# PaxInstrument-T400.net
KiCad netlist of a schematic drawn in EAGLE
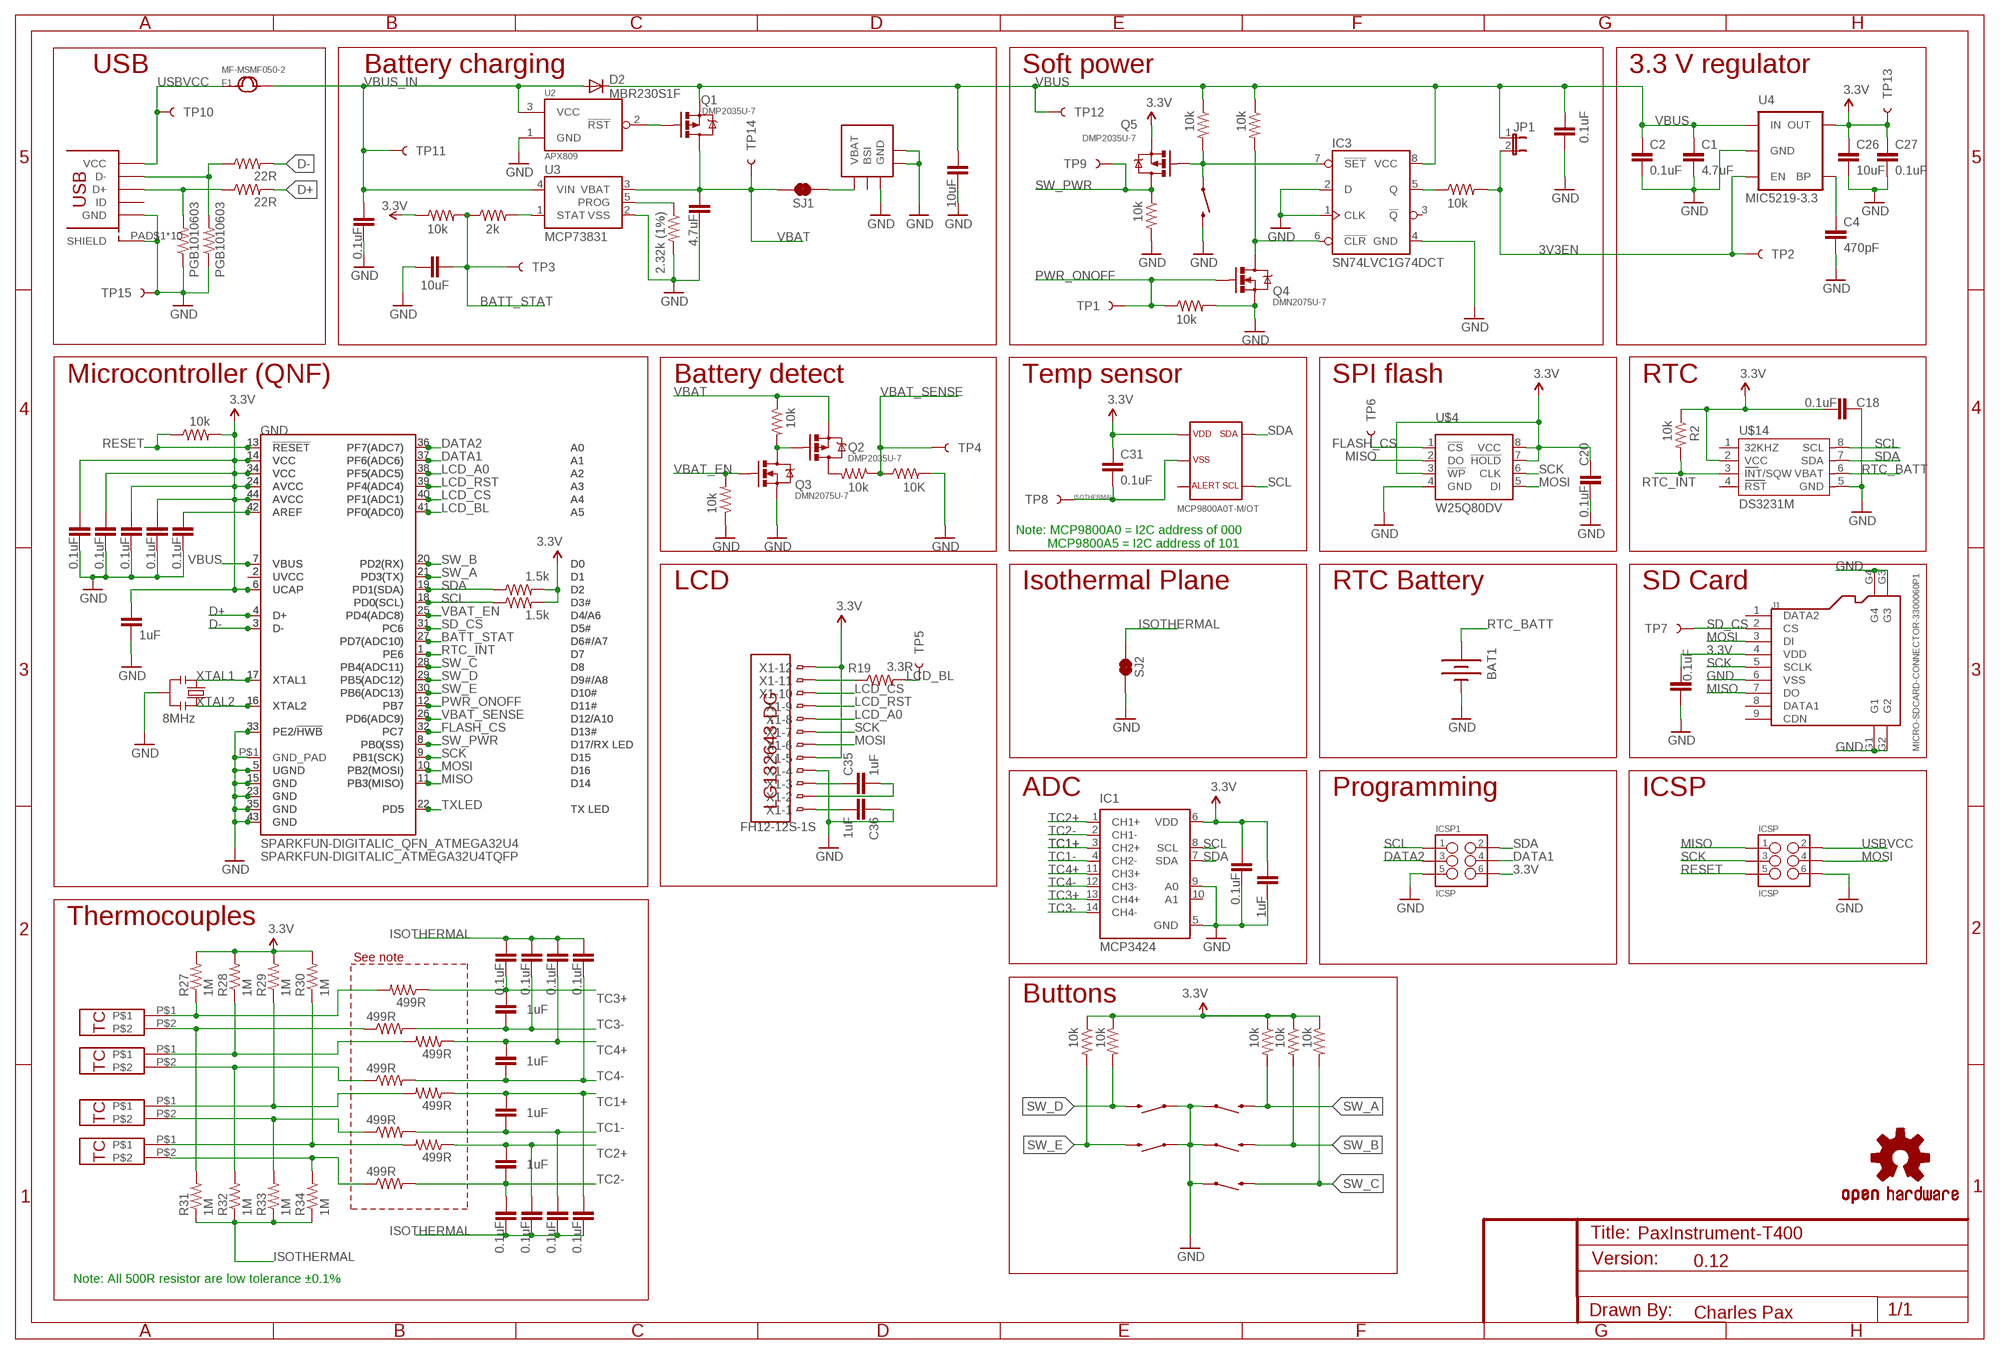
[diagram p0: schematic, sheet 1]

(export (version "E")
  (design (tool "Eeschema 10.0.6"))
  (components
    (comp (ref "BAT1")
      (value "BATTERY12MM")
      (footprint "eagle-import:BATTCON_12MM")
      (fields (field (name "MF") "Keystone Electronics") (field (name "MPN") "3000TR"))
      (libsource (lib "eagle-import") (part "BATTERY12MM"))
    )
    (comp (ref "C1")
      (value "4.7uF")
      (footprint "eagle-import:SPARKFUN-CAPACITORS_0603-CAP")
      (libsource (lib "eagle-import") (part "SPARKFUN-CAPACITORS_CAP0603-CAP"))
    )
    (comp (ref "C2")
      (value "0.1uF")
      (footprint "eagle-import:SPARKFUN-CAPACITORS_0603-CAP")
      (libsource (lib "eagle-import") (part "SPARKFUN-CAPACITORS_CAP0603-CAP"))
    )
    (comp (ref "C3")
      (value "0.1uF")
      (footprint "eagle-import:SPARKFUN-CAPACITORS_0603-CAP")
      (libsource (lib "eagle-import") (part "SPARKFUN-CAPACITORS_CAP0603-CAP"))
    )
    (comp (ref "C4")
      (value "470pF")
      (footprint "eagle-import:SPARKFUN-CAPACITORS_0603-CAP")
      (libsource (lib "eagle-import") (part "SPARKFUN-CAPACITORS_CAP0603-CAP"))
    )
    (comp (ref "C5")
      (value "0.1uF")
      (footprint "eagle-import:SPARKFUN-CAPACITORS_0603-CAP")
      (libsource (lib "eagle-import") (part "SPARKFUN-CAPACITORS_CAP0603-CAP"))
    )
    (comp (ref "C6")
      (value "0.1uF")
      (footprint "eagle-import:SPARKFUN-CAPACITORS_0603-CAP")
      (libsource (lib "eagle-import") (part "SPARKFUN-CAPACITORS_CAP0603-CAP"))
    )
    (comp (ref "C7")
      (value "1uF")
      (footprint "eagle-import:SPARKFUN-CAPACITORS_0603-CAP")
      (libsource (lib "eagle-import") (part "SPARKFUN-CAPACITORS_CAP0603-CAP"))
    )
    (comp (ref "C8")
      (value "1uF")
      (footprint "eagle-import:SPARKFUN-CAPACITORS_0603-CAP")
      (libsource (lib "eagle-import") (part "SPARKFUN-CAPACITORS_CAP0603-CAP"))
    )
    (comp (ref "C9")
      (value "4.7uF")
      (footprint "eagle-import:SPARKFUN-CAPACITORS_0603-CAP")
      (libsource (lib "eagle-import") (part "SPARKFUN-CAPACITORS_CAP0603-CAP"))
    )
    (comp (ref "C10")
      (value "1uF")
      (footprint "eagle-import:SPARKFUN-CAPACITORS_0603-CAP")
      (libsource (lib "eagle-import") (part "SPARKFUN-CAPACITORS_CAP0603-CAP"))
    )
    (comp (ref "C11")
      (value "1uF")
      (footprint "eagle-import:SPARKFUN-CAPACITORS_0603-CAP")
      (libsource (lib "eagle-import") (part "SPARKFUN-CAPACITORS_CAP0603-CAP"))
    )
    (comp (ref "C12")
      (value "10uF")
      (footprint "eagle-import:SPARKFUN-CAPACITORS_0603-CAP")
      (libsource (lib "eagle-import") (part "SPARKFUN-CAPACITORS_CAP0603-CAP"))
    )
    (comp (ref "C13")
      (value "0.1uF")
      (footprint "eagle-import:SPARKFUN-CAPACITORS_0603-CAP")
      (libsource (lib "eagle-import") (part "SPARKFUN-CAPACITORS_CAP0603-CAP"))
    )
    (comp (ref "C14")
      (value "0.1uF")
      (footprint "eagle-import:SPARKFUN-CAPACITORS_0603-CAP")
      (libsource (lib "eagle-import") (part "SPARKFUN-CAPACITORS_CAP0603-CAP"))
    )
    (comp (ref "C15")
      (value "0.1uF")
      (footprint "eagle-import:SPARKFUN-CAPACITORS_0603-CAP")
      (libsource (lib "eagle-import") (part "SPARKFUN-CAPACITORS_CAP0603-CAP"))
    )
    (comp (ref "C16")
      (value "0.1uF")
      (footprint "eagle-import:SPARKFUN-CAPACITORS_0603-CAP")
      (libsource (lib "eagle-import") (part "SPARKFUN-CAPACITORS_CAP0603-CAP"))
    )
    (comp (ref "C17")
      (value "0.1uF")
      (footprint "eagle-import:SPARKFUN-CAPACITORS_0603-CAP")
      (libsource (lib "eagle-import") (part "SPARKFUN-CAPACITORS_CAP0603-CAP"))
    )
    (comp (ref "C18")
      (value "0.1uF")
      (footprint "eagle-import:SPARKFUN-CAPACITORS_0603-CAP")
      (libsource (lib "eagle-import") (part "SPARKFUN-CAPACITORS_CAP0603-CAP"))
    )
    (comp (ref "C19")
      (value "1uF")
      (footprint "eagle-import:SPARKFUN-CAPACITORS_0603-CAP")
      (libsource (lib "eagle-import") (part "SPARKFUN-CAPACITORS_CAP0603-CAP"))
    )
    (comp (ref "C20")
      (value "0.1uF")
      (footprint "eagle-import:SPARKFUN-CAPACITORS_0603-CAP")
      (libsource (lib "eagle-import") (part "SPARKFUN-CAPACITORS_CAP0603-CAP"))
    )
    (comp (ref "C21")
      (value "0.1uF")
      (footprint "eagle-import:SPARKFUN-CAPACITORS_0603-CAP")
      (libsource (lib "eagle-import") (part "SPARKFUN-CAPACITORS_CAP0603-CAP"))
    )
    (comp (ref "C22")
      (value "10uF")
      (footprint "eagle-import:SPARKFUN-CAPACITORS_0603-CAP")
      (libsource (lib "eagle-import") (part "SPARKFUN-CAPACITORS_CAP0603-CAP"))
    )
    (comp (ref "C24")
      (value "0.1uF")
      (footprint "eagle-import:SPARKFUN-CAPACITORS_0603-CAP")
      (libsource (lib "eagle-import") (part "SPARKFUN-CAPACITORS_CAP0603-CAP"))
    )
    (comp (ref "C25")
      (value "0.1uF")
      (footprint "eagle-import:SPARKFUN-CAPACITORS_0603-CAP")
      (libsource (lib "eagle-import") (part "SPARKFUN-CAPACITORS_CAP0603-CAP"))
    )
    (comp (ref "C26")
      (value "10uF")
      (footprint "eagle-import:SPARKFUN-CAPACITORS_0603-CAP")
      (libsource (lib "eagle-import") (part "SPARKFUN-CAPACITORS_CAP0603-CAP"))
    )
    (comp (ref "C27")
      (value "0.1uF")
      (footprint "eagle-import:SPARKFUN-CAPACITORS_0603-CAP")
      (libsource (lib "eagle-import") (part "SPARKFUN-CAPACITORS_CAP0603-CAP"))
    )
    (comp (ref "C28")
      (value "0.1uF")
      (footprint "eagle-import:SPARKFUN-CAPACITORS_0603-CAP")
      (libsource (lib "eagle-import") (part "SPARKFUN-CAPACITORS_CAP0603-CAP"))
    )
    (comp (ref "C29")
      (value "0.1uF")
      (footprint "eagle-import:SPARKFUN-CAPACITORS_0603-CAP")
      (libsource (lib "eagle-import") (part "SPARKFUN-CAPACITORS_CAP0603-CAP"))
    )
    (comp (ref "C30")
      (value "1uF")
      (footprint "eagle-import:SPARKFUN-CAPACITORS_0603-CAP")
      (libsource (lib "eagle-import") (part "SPARKFUN-CAPACITORS_CAP0603-CAP"))
    )
    (comp (ref "C31")
      (value "0.1uF")
      (footprint "eagle-import:SPARKFUN-CAPACITORS_0603-CAP")
      (libsource (lib "eagle-import") (part "SPARKFUN-CAPACITORS_CAP0603-CAP"))
    )
    (comp (ref "C32")
      (value "0.1uF")
      (footprint "eagle-import:SPARKFUN-CAPACITORS_0603-CAP")
      (libsource (lib "eagle-import") (part "SPARKFUN-CAPACITORS_CAP0603-CAP"))
    )
    (comp (ref "C33")
      (value "0.1uF")
      (footprint "eagle-import:SPARKFUN-CAPACITORS_0603-CAP")
      (libsource (lib "eagle-import") (part "SPARKFUN-CAPACITORS_CAP0603-CAP"))
    )
    (comp (ref "C34")
      (value "0.1uF")
      (footprint "eagle-import:SPARKFUN-CAPACITORS_0603-CAP")
      (libsource (lib "eagle-import") (part "SPARKFUN-CAPACITORS_CAP0603-CAP"))
    )
    (comp (ref "C35")
      (value "1uF")
      (footprint "eagle-import:SPARKFUN-CAPACITORS_0603-CAP")
      (libsource (lib "eagle-import") (part "SPARKFUN-CAPACITORS_CAP0603-CAP"))
    )
    (comp (ref "C36")
      (value "1uF")
      (footprint "eagle-import:SPARKFUN-CAPACITORS_0603-CAP")
      (libsource (lib "eagle-import") (part "SPARKFUN-CAPACITORS_CAP0603-CAP"))
    )
    (comp (ref "C37")
      (value "0.1uF")
      (footprint "eagle-import:SPARKFUN-CAPACITORS_0603-CAP")
      (libsource (lib "eagle-import") (part "SPARKFUN-CAPACITORS_CAP0603-CAP"))
    )
    (comp (ref "D2")
      (value "MBR230S1F")
      (footprint "eagle-import:SOD123")
      (fields (field (name "MF") "DIODES INC") (field (name "MPN") "MBR230S1F-7"))
      (libsource (lib "eagle-import") (part "SPARKFUN-DISCRETESEMI_DIODESOD123SOD123"))
    )
    (comp (ref "F1")
      (value "FUSE-1812")
      (footprint "eagle-import:F1812")
      (fields (field (name "MF") "Bourns") (field (name "MPN") "MF-MSMF050-2"))
      (libsource (lib "eagle-import") (part "FUSE-1812"))
    )
    (comp (ref "GND")
      (value "SPARKFUN-DIGITALIC_QFN_ATMEGA32U4")
      (footprint "eagle-import:SPARKFUN-DIGITALIC_SPARKFUN-DIGITALIC_QFN-44")
      (fields (field (name "MF") "Atmel") (field (name "MPN") "ATMEGA32U4-MU"))
      (libsource (lib "eagle-import") (part "SPARKFUN-DIGITALIC_QFN_ATMEGA32U4"))
    )
    (comp (ref "IC1")
      (value "MCP3424")
      (footprint "eagle-import:SO14")
      (fields (field (name "MF") "Microchip Technology") (field (name "MPN") "MCP3424-E/SL"))
      (libsource (lib "eagle-import") (part "MCP3424"))
    )
    (comp (ref "IC3")
      (value "SN74LVC1G74DCT")
      (footprint "eagle-import:SSOP8")
      (fields (field (name "MF") "Texas Instruments") (field (name "MPN") "SN74LVC1G74DCTR "))
      (libsource (lib "eagle-import") (part "SN74LVC1G74DCT"))
    )
    (comp (ref "ICSP")
      (value "ICSP")
      (footprint "eagle-import:SPARKFUN-CONNECTORS_2X3_SMT_POSTS_PAXINSTRUMENT")
      (fields (field (name "MF") "FCI") (field (name "MPN") "95278-101A06LF"))
      (libsource (lib "eagle-import") (part "SPARKFUN-CONNECTORS_M03X2PAX"))
    )
    (comp (ref "ICSP1")
      (value "ICSP")
      (footprint "eagle-import:SPARKFUN-CONNECTORS_2X3_SMT_POSTS_PAXINSTRUMENT")
      (fields (field (name "MF") "FCI") (field (name "MPN") "95278-101A06LF"))
      (libsource (lib "eagle-import") (part "SPARKFUN-CONNECTORS_M03X2PAX"))
    )
    (comp (ref "J1")
      (value "MICRO-SDCARD-CONNECTOR-3300060P1")
      (footprint "eagle-import:9P-SMD-W-RING")
      (fields (field (name "MF") "SUNTECH") (field (name "MPN") "ST-TF-003A"))
      (libsource (lib "eagle-import") (part "MICRO-SDCARD-CONNECTOR-3300060P1"))
    )
    (comp (ref "JP1")
      (value "JUMPER-2SMD-NO")
      (footprint "eagle-import:SJ_2S-NO")
      (libsource (lib "eagle-import") (part "JUMPER-2SMD-NO"))
    )
    (comp (ref "LOGO1")
      (value "OSHW-LOGOS")
      (footprint "eagle-import:OSHW-LOGO-S")
      (libsource (lib "eagle-import") (part "OSHW-LOGOS"))
    )
    (comp (ref "Q1")
      (value "DMP2035U-7")
      (footprint "eagle-import:SOT23")
      (fields (field (name "MF") "DIODES INC"))
      (libsource (lib "eagle-import") (part "MOSFET-PCHANNELSMT"))
    )
    (comp (ref "Q2")
      (value "DMP2035U-7")
      (footprint "eagle-import:SOT23")
      (fields (field (name "MF") "DIODES INC"))
      (libsource (lib "eagle-import") (part "MOSFET-PCHANNELSMT"))
    )
    (comp (ref "Q3")
      (value "DMN2075U-7")
      (footprint "eagle-import:SOT23")
      (fields (field (name "MF") "DIODES INC") (field (name "MPN") "DMN2075U-7 "))
      (libsource (lib "eagle-import") (part "MOSFET-NCHANNELSMT"))
    )
    (comp (ref "Q4")
      (value "DMN2075U-7")
      (footprint "eagle-import:SOT23")
      (fields (field (name "MF") "DIODES INC") (field (name "MPN") "DMN2075U-7 "))
      (libsource (lib "eagle-import") (part "MOSFET-NCHANNELSMT"))
    )
    (comp (ref "Q5")
      (value "DMP2035U-7")
      (footprint "eagle-import:SOT23")
      (fields (field (name "MF") "DIODES INC"))
      (libsource (lib "eagle-import") (part "MOSFET-PCHANNELSMT"))
    )
    (comp (ref "R1")
      (value "10k")
      (footprint "eagle-import:SPARKFUN-RESISTORS_0603-RES")
      (libsource (lib "eagle-import") (part "SPARKFUN-RESISTORS_RESISTOR0603-RES"))
    )
    (comp (ref "R2")
      (value "10k")
      (footprint "eagle-import:SPARKFUN-RESISTORS_0603-RES")
      (libsource (lib "eagle-import") (part "SPARKFUN-RESISTORS_RESISTOR0603-RES"))
    )
    (comp (ref "R3")
      (value "2.32k (1%)")
      (footprint "eagle-import:SPARKFUN-RESISTORS_0603-RES")
      (libsource (lib "eagle-import") (part "SPARKFUN-RESISTORS_RESISTOR0603-RES"))
    )
    (comp (ref "R4")
      (value "10k")
      (footprint "eagle-import:SPARKFUN-RESISTORS_0603-RES")
      (libsource (lib "eagle-import") (part "SPARKFUN-RESISTORS_RESISTOR0603-RES"))
    )
    (comp (ref "R5")
      (value "10k")
      (footprint "eagle-import:SPARKFUN-RESISTORS_0603-RES")
      (libsource (lib "eagle-import") (part "SPARKFUN-RESISTORS_RESISTOR0603-RES"))
    )
    (comp (ref "R6")
      (value "10k")
      (footprint "eagle-import:SPARKFUN-RESISTORS_0603-RES")
      (libsource (lib "eagle-import") (part "SPARKFUN-RESISTORS_RESISTOR0603-RES"))
    )
    (comp (ref "R7")
      (value "10k")
      (footprint "eagle-import:SPARKFUN-RESISTORS_0603-RES")
      (libsource (lib "eagle-import") (part "SPARKFUN-RESISTORS_RESISTOR0603-RES"))
    )
    (comp (ref "R8")
      (value "10k")
      (footprint "eagle-import:SPARKFUN-RESISTORS_0603-RES")
      (libsource (lib "eagle-import") (part "SPARKFUN-RESISTORS_RESISTOR0603-RES"))
    )
    (comp (ref "R9")
      (value "22R")
      (footprint "eagle-import:SPARKFUN-RESISTORS_0603-RES")
      (libsource (lib "eagle-import") (part "SPARKFUN-RESISTORS_RESISTOR0603-RES"))
    )
    (comp (ref "R10")
      (value "22R")
      (footprint "eagle-import:SPARKFUN-RESISTORS_0603-RES")
      (libsource (lib "eagle-import") (part "SPARKFUN-RESISTORS_RESISTOR0603-RES"))
    )
    (comp (ref "R11")
      (value "10k")
      (footprint "eagle-import:SPARKFUN-RESISTORS_0603-RES")
      (libsource (lib "eagle-import") (part "SPARKFUN-RESISTORS_RESISTOR0603-RES"))
    )
    (comp (ref "R12")
      (value "10k")
      (footprint "eagle-import:SPARKFUN-RESISTORS_0603-RES")
      (libsource (lib "eagle-import") (part "SPARKFUN-RESISTORS_RESISTOR0603-RES"))
    )
    (comp (ref "R13")
      (value "1.5k")
      (footprint "eagle-import:SPARKFUN-RESISTORS_0603-RES")
      (libsource (lib "eagle-import") (part "SPARKFUN-RESISTORS_RESISTOR0603-RES"))
    )
    (comp (ref "R14")
      (value "1.5k")
      (footprint "eagle-import:SPARKFUN-RESISTORS_0603-RES")
      (libsource (lib "eagle-import") (part "SPARKFUN-RESISTORS_RESISTOR0603-RES"))
    )
    (comp (ref "R15")
      (value "10k")
      (footprint "eagle-import:SPARKFUN-RESISTORS_0603-RES")
      (libsource (lib "eagle-import") (part "SPARKFUN-RESISTORS_RESISTOR0603-RES"))
    )
    (comp (ref "R16")
      (value "10k")
      (footprint "eagle-import:SPARKFUN-RESISTORS_0603-RES")
      (libsource (lib "eagle-import") (part "SPARKFUN-RESISTORS_RESISTOR0603-RES"))
    )
    (comp (ref "R17")
      (value "2k")
      (footprint "eagle-import:SPARKFUN-RESISTORS_0603-RES")
      (libsource (lib "eagle-import") (part "SPARKFUN-RESISTORS_RESISTOR0603-RES"))
    )
    (comp (ref "R18")
      (value "10k")
      (footprint "eagle-import:SPARKFUN-RESISTORS_0603-RES")
      (libsource (lib "eagle-import") (part "SPARKFUN-RESISTORS_RESISTOR0603-RES"))
    )
    (comp (ref "R19")
      (value "3.3R")
      (footprint "eagle-import:SPARKFUN-RESISTORS_0603-RES")
      (libsource (lib "eagle-import") (part "SPARKFUN-RESISTORS_RESISTOR0603-RES"))
    )
    (comp (ref "R20")
      (value "10k")
      (footprint "eagle-import:SPARKFUN-RESISTORS_0603-RES")
      (libsource (lib "eagle-import") (part "SPARKFUN-RESISTORS_RESISTOR0603-RES"))
    )
    (comp (ref "R21")
      (value "10k")
      (footprint "eagle-import:SPARKFUN-RESISTORS_0603-RES")
      (libsource (lib "eagle-import") (part "SPARKFUN-RESISTORS_RESISTOR0603-RES"))
    )
    (comp (ref "R22")
      (value "10k")
      (footprint "eagle-import:SPARKFUN-RESISTORS_0603-RES")
      (libsource (lib "eagle-import") (part "SPARKFUN-RESISTORS_RESISTOR0603-RES"))
    )
    (comp (ref "R23")
      (value "10k")
      (footprint "eagle-import:SPARKFUN-RESISTORS_0603-RES")
      (libsource (lib "eagle-import") (part "SPARKFUN-RESISTORS_RESISTOR0603-RES"))
    )
    (comp (ref "R24")
      (value "10K")
      (footprint "eagle-import:SPARKFUN-RESISTORS_0603-RES")
      (libsource (lib "eagle-import") (part "SPARKFUN-RESISTORS_RESISTOR0603-RES"))
    )
    (comp (ref "R27")
      (value "1M")
      (footprint "eagle-import:SPARKFUN-RESISTORS_0603-RES")
      (libsource (lib "eagle-import") (part "SPARKFUN-RESISTORS_RESISTOR0603-RES"))
    )
    (comp (ref "R28")
      (value "1M")
      (footprint "eagle-import:SPARKFUN-RESISTORS_0603-RES")
      (libsource (lib "eagle-import") (part "SPARKFUN-RESISTORS_RESISTOR0603-RES"))
    )
    (comp (ref "R29")
      (value "1M")
      (footprint "eagle-import:SPARKFUN-RESISTORS_0603-RES")
      (libsource (lib "eagle-import") (part "SPARKFUN-RESISTORS_RESISTOR0603-RES"))
    )
    (comp (ref "R30")
      (value "1M")
      (footprint "eagle-import:SPARKFUN-RESISTORS_0603-RES")
      (libsource (lib "eagle-import") (part "SPARKFUN-RESISTORS_RESISTOR0603-RES"))
    )
    (comp (ref "R31")
      (value "1M")
      (footprint "eagle-import:SPARKFUN-RESISTORS_0603-RES")
      (libsource (lib "eagle-import") (part "SPARKFUN-RESISTORS_RESISTOR0603-RES"))
    )
    (comp (ref "R32")
      (value "1M")
      (footprint "eagle-import:SPARKFUN-RESISTORS_0603-RES")
      (libsource (lib "eagle-import") (part "SPARKFUN-RESISTORS_RESISTOR0603-RES"))
    )
    (comp (ref "R33")
      (value "1M")
      (footprint "eagle-import:SPARKFUN-RESISTORS_0603-RES")
      (libsource (lib "eagle-import") (part "SPARKFUN-RESISTORS_RESISTOR0603-RES"))
    )
    (comp (ref "R34")
      (value "1M")
      (footprint "eagle-import:SPARKFUN-RESISTORS_0603-RES")
      (libsource (lib "eagle-import") (part "SPARKFUN-RESISTORS_RESISTOR0603-RES"))
    )
    (comp (ref "R35")
      (value "499R")
      (footprint "eagle-import:SPARKFUN-RESISTORS_0603-RES")
      (fields (field (name "MF") "Vishay") (field (name "MPN") "TNPW0603499RBEEA"))
      (libsource (lib "eagle-import") (part "SPARKFUN-RESISTORS_RESISTOR0603-RES"))
    )
    (comp (ref "R36")
      (value "499R")
      (footprint "eagle-import:SPARKFUN-RESISTORS_0603-RES")
      (fields (field (name "MF") "Vishay") (field (name "MPN") "TNPW0603499RBEEA"))
      (libsource (lib "eagle-import") (part "SPARKFUN-RESISTORS_RESISTOR0603-RES"))
    )
    (comp (ref "R37")
      (value "499R")
      (footprint "eagle-import:SPARKFUN-RESISTORS_0603-RES")
      (fields (field (name "MF") "Vishay") (field (name "MPN") "TNPW0603499RBEEA"))
      (libsource (lib "eagle-import") (part "SPARKFUN-RESISTORS_RESISTOR0603-RES"))
    )
    (comp (ref "R38")
      (value "499R")
      (footprint "eagle-import:SPARKFUN-RESISTORS_0603-RES")
      (fields (field (name "MF") "Vishay") (field (name "MPN") "TNPW0603499RBEEA"))
      (libsource (lib "eagle-import") (part "SPARKFUN-RESISTORS_RESISTOR0603-RES"))
    )
    (comp (ref "R39")
      (value "499R")
      (footprint "eagle-import:SPARKFUN-RESISTORS_0603-RES")
      (fields (field (name "MF") "Vishay") (field (name "MPN") "TNPW0603499RBEEA"))
      (libsource (lib "eagle-import") (part "SPARKFUN-RESISTORS_RESISTOR0603-RES"))
    )
    (comp (ref "R40")
      (value "499R")
      (footprint "eagle-import:SPARKFUN-RESISTORS_0603-RES")
      (fields (field (name "MF") "Vishay") (field (name "MPN") "TNPW0603499RBEEA"))
      (libsource (lib "eagle-import") (part "SPARKFUN-RESISTORS_RESISTOR0603-RES"))
    )
    (comp (ref "R41")
      (value "499R")
      (footprint "eagle-import:SPARKFUN-RESISTORS_0603-RES")
      (fields (field (name "MF") "Vishay") (field (name "MPN") "TNPW0603499RBEEA"))
      (libsource (lib "eagle-import") (part "SPARKFUN-RESISTORS_RESISTOR0603-RES"))
    )
    (comp (ref "R42")
      (value "499R")
      (footprint "eagle-import:SPARKFUN-RESISTORS_0603-RES")
      (fields (field (name "MF") "Vishay") (field (name "MPN") "TNPW0603499RBEEA"))
      (libsource (lib "eagle-import") (part "SPARKFUN-RESISTORS_RESISTOR0603-RES"))
    )
    (comp (ref "S1")
      (value "SWITCH-MOMENTARY-2SMD")
      (footprint "eagle-import:TACTILE_SWITCH_SMD")
      (fields (field (name "MF") "C&K Components") (field (name "MPN") "RS-187R05A2-DS MT RT"))
      (libsource (lib "eagle-import") (part "SWITCH-MOMENTARY-2SMD"))
    )
    (comp (ref "S2")
      (value "SWITCH-MOMENTARY-2SMD")
      (footprint "eagle-import:TACTILE_SWITCH_SMD")
      (fields (field (name "MF") "C&K Components") (field (name "MPN") "RS-187R05A2-DS MT RT"))
      (libsource (lib "eagle-import") (part "SWITCH-MOMENTARY-2SMD"))
    )
    (comp (ref "S3")
      (value "SWITCH-MOMENTARY-2SMD")
      (footprint "eagle-import:TACTILE_SWITCH_SMD")
      (fields (field (name "MF") "C&K Components") (field (name "MPN") "RS-187R05A2-DS MT RT"))
      (libsource (lib "eagle-import") (part "SWITCH-MOMENTARY-2SMD"))
    )
    (comp (ref "S4")
      (value "SWITCH-MOMENTARY-2SMD")
      (footprint "eagle-import:TACTILE_SWITCH_SMD")
      (fields (field (name "MF") "C&K Components") (field (name "MPN") "RS-187R05A2-DS MT RT"))
      (libsource (lib "eagle-import") (part "SWITCH-MOMENTARY-2SMD"))
    )
    (comp (ref "S5")
      (value "SWITCH-MOMENTARY-2SMD")
      (footprint "eagle-import:TACTILE_SWITCH_SMD")
      (fields (field (name "MF") "C&K Components") (field (name "MPN") "RS-187R05A2-DS MT RT"))
      (libsource (lib "eagle-import") (part "SWITCH-MOMENTARY-2SMD"))
    )
    (comp (ref "S6")
      (value "SWITCH-MOMENTARY-2SMD")
      (footprint "eagle-import:TACTILE_SWITCH_SMD")
      (fields (field (name "MF") "C&K Components") (field (name "MPN") "RS-187R05A2-DS MT RT"))
      (libsource (lib "eagle-import") (part "SWITCH-MOMENTARY-2SMD"))
    )
    (comp (ref "SJ1")
      (value "JUMPER-PAD-2-NC_BY_TRACE")
      (footprint "eagle-import:PAD-JUMPER-2-NC_BY_TRACE_YES_SILK")
      (libsource (lib "eagle-import") (part "JUMPER-PAD-2-NC_BY_TRACE"))
    )
    (comp (ref "SJ2")
      (value "JUMPER-PAD-2-NC_BY_TRACE")
      (footprint "eagle-import:PAD-JUMPER-2-NC_BY_TRACE_YES_SILK")
      (libsource (lib "eagle-import") (part "JUMPER-PAD-2-NC_BY_TRACE"))
    )
    (comp (ref "TP1")
      (value "PWR_ONOFF")
      (footprint "eagle-import:TP_15TH")
      (libsource (lib "eagle-import") (part "TEST-POINTTP_15TH_THRU"))
    )
    (comp (ref "TP2")
      (value "3V3_EN")
      (footprint "eagle-import:TP_15TH")
      (libsource (lib "eagle-import") (part "TEST-POINTTP_15TH_THRU"))
    )
    (comp (ref "TP3")
      (value "BATT_STAT")
      (footprint "eagle-import:TP_15TH")
      (libsource (lib "eagle-import") (part "TEST-POINTTP_15TH_THRU"))
    )
    (comp (ref "TP4")
      (value "VBAT_SENSE")
      (footprint "eagle-import:TP_15TH")
      (libsource (lib "eagle-import") (part "TEST-POINTTP_15TH_THRU"))
    )
    (comp (ref "TP5")
      (value "LCD_BL")
      (footprint "eagle-import:TP_15TH")
      (libsource (lib "eagle-import") (part "TEST-POINTTP_15TH_THRU"))
    )
    (comp (ref "TP6")
      (value "FLASH_CS")
      (footprint "eagle-import:TP_15TH")
      (libsource (lib "eagle-import") (part "TEST-POINTTP_15TH_THRU"))
    )
    (comp (ref "TP7")
      (value "SD_CS")
      (footprint "eagle-import:TP_15TH")
      (libsource (lib "eagle-import") (part "TEST-POINTTP_15TH_THRU"))
    )
    (comp (ref "TP8")
      (value "ISOTHERMAL")
      (footprint "eagle-import:TP_15TH")
      (libsource (lib "eagle-import") (part "TEST-POINTTP_15TH_THRU"))
    )
    (comp (ref "TP9")
      (value "SW_PWR")
      (footprint "eagle-import:TP_15TH")
      (libsource (lib "eagle-import") (part "TEST-POINTTP_15TH_THRU"))
    )
    (comp (ref "TP10")
      (value "TEST-POINTTP_15TH_THRU")
      (footprint "eagle-import:TP_15TH")
      (libsource (lib "eagle-import") (part "TEST-POINTTP_15TH_THRU"))
    )
    (comp (ref "TP11")
      (value "VBUS_IN")
      (footprint "eagle-import:TP_15TH")
      (libsource (lib "eagle-import") (part "TEST-POINTTP_15TH_THRU"))
    )
    (comp (ref "TP12")
      (value "VBUS")
      (footprint "eagle-import:TP_15TH")
      (libsource (lib "eagle-import") (part "TEST-POINTTP_15TH_THRU"))
    )
    (comp (ref "TP13")
      (value "3.3V")
      (footprint "eagle-import:TP_15TH")
      (libsource (lib "eagle-import") (part "TEST-POINTTP_15TH_THRU"))
    )
    (comp (ref "TP14")
      (value "VBAT")
      (footprint "eagle-import:TP_15TH")
      (libsource (lib "eagle-import") (part "TEST-POINTTP_15TH_THRU"))
    )
    (comp (ref "TP15")
      (value "GND")
      (footprint "eagle-import:TP_15TH")
      (libsource (lib "eagle-import") (part "TEST-POINTTP_15TH_THRU"))
    )
    (comp (ref "U$1")
      (value "USB_MICROSMT+THRUHULE")
      (footprint "eagle-import:USB_MICRO_THRUHOLE")
      (fields (field (name "MF") "FCI") (field (name "MPN") "10118194-0001LF"))
      (libsource (lib "eagle-import") (part "USB_MICROSMT+THRUHULE"))
    )
    (comp (ref "U$2")
      (value "BL-5C-CONNECTOR")
      (footprint "eagle-import:BL-5C-CONNECTOR")
      (fields (field (name "MPN") "BC-4-3P (77H)"))
      (libsource (lib "eagle-import") (part "BL-5C-CONNECTOR"))
    )
    (comp (ref "U$3")
      (value "SPARKFUN-DIGITALIC_ATMEGA32U4TQFP")
      (footprint "eagle-import:SPARKFUN-DIGITALIC_SPARKFUN-DIGITALIC_TQFP44")
      (fields (field (name "MF") "Atmel") (field (name "MPN") "ATMEGA32U4-AU"))
      (libsource (lib "eagle-import") (part "SPARKFUN-DIGITALIC_ATMEGA32U4TQFP"))
    )
    (comp (ref "U$4")
      (value "W25Q80DV")
      (footprint "eagle-import:CHARLESPAX_SOIC8M")
      (fields (field (name "MF") "Winbond Electronics") (field (name "MPN") "W25Q80DVSSIG-ND"))
      (libsource (lib "eagle-import") (part "W25Q80BV"))
    )
    (comp (ref "U$5")
      (value "LG132643-DG")
      (footprint "eagle-import:LG132643-DG")
      (fields (field (name "MPN") "LG132643-DW"))
      (libsource (lib "eagle-import") (part "LG132643-DG"))
    )
    (comp (ref "U$10")
      (value "TC-MINI-CONNECTOR1024")
      (footprint "eagle-import:1024-TC-CONNECTOR")
      (fields (field (name "MF") "Keystone") (field (name "MPN") "3572"))
      (libsource (lib "eagle-import") (part "TC-MINI-CONNECTOR1024"))
    )
    (comp (ref "U$11")
      (value "TC-MINI-CONNECTOR1024")
      (footprint "eagle-import:1024-TC-CONNECTOR")
      (fields (field (name "MF") "Keystone") (field (name "MPN") "3572"))
      (libsource (lib "eagle-import") (part "TC-MINI-CONNECTOR1024"))
    )
    (comp (ref "U$12")
      (value "TC-MINI-CONNECTOR1024")
      (footprint "eagle-import:1024-TC-CONNECTOR")
      (fields (field (name "MF") "Keystone") (field (name "MPN") "3572"))
      (libsource (lib "eagle-import") (part "TC-MINI-CONNECTOR1024"))
    )
    (comp (ref "U$13")
      (value "TC-MINI-CONNECTOR1024")
      (footprint "eagle-import:1024-TC-CONNECTOR")
      (fields (field (name "MF") "Keystone") (field (name "MPN") "3572"))
      (libsource (lib "eagle-import") (part "TC-MINI-CONNECTOR1024"))
    )
    (comp (ref "U$14")
      (value "DS3231M")
      (footprint "eagle-import:SOIC8")
      (fields (field (name "MF") "Maxim Integrated") (field (name "MPN") "DS3231MZ+"))
      (libsource (lib "eagle-import") (part "DS3231M"))
    )
    (comp (ref "U1")
      (value "MCP9800")
      (footprint "eagle-import:SOT23-5L")
      (fields (field (name "MF") "Microchip Technology") (field (name "MPN") "MCP9800A0T-M/OT"))
      (libsource (lib "eagle-import") (part "MCP9800"))
    )
    (comp (ref "U2")
      (value "APX809")
      (footprint "eagle-import:SOT23")
      (fields (field (name "MF") "DIODES INC") (field (name "MPN") "APX809-44SAG-7"))
      (libsource (lib "eagle-import") (part "APX809"))
    )
    (comp (ref "U3")
      (value "MCP73831")
      (footprint "eagle-import:SOT23-5")
      (fields (field (name "MF") "Microchip Technology") (field (name "MPN") "MCP73832T-2DCI/OT"))
      (libsource (lib "eagle-import") (part "MCP73831"))
    )
    (comp (ref "U4")
      (value "MIC5219-3.3V")
      (footprint "eagle-import:SOT23-5")
      (fields (field (name "MF") "Micrel") (field (name "MPN") "MIC5219-3.3YM5 TR"))
      (libsource (lib "eagle-import") (part "V_REG_LDOSMD"))
    )
    (comp (ref "X1")
      (value "FH12-12S-1S")
      (footprint "eagle-import:FH12-12S-1SH")
      (fields (field (name "MF") "Hirose Connector") (field (name "MPN") "FH12-12S-1SH(55)"))
      (libsource (lib "eagle-import") (part "FH12-12S-1S"))
    )
    (comp (ref "Y1")
      (value "RESONATORSMD")
      (footprint "eagle-import:RESONATOR-SMD")
      (fields (field (name "MF") "Murata Electronics") (field (name "MPN") "CSTCE8M00G52-R0"))
      (libsource (lib "eagle-import") (part "RESONATORSMD"))
    )
    (comp (ref "Z1")
      (value "PGB1010603")
      (footprint "eagle-import:SPARKFUN-RESISTORS_0603-RES")
      (fields (field (name "MF") "Littelfuse") (field (name "MPN") "PGB1010603NRHF"))
      (libsource (lib "eagle-import") (part "SPARKFUN-RESISTORS_RESISTOR0603-RES"))
    )
    (comp (ref "Z2")
      (value "PGB1010603")
      (footprint "eagle-import:SPARKFUN-RESISTORS_0603-RES")
      (fields (field (name "MF") "Littelfuse") (field (name "MPN") "PGB1010603NRHF"))
      (libsource (lib "eagle-import") (part "SPARKFUN-RESISTORS_RESISTOR0603-RES"))
    )
  )
  (nets
    (net (code "1") (name "/3V3EN") (class "Default")
      (node (ref "JP1") (pin "2") (pinfunction "2_2") (pintype "passive"))
      (node (ref "R21") (pin "2") (pinfunction "2_2") (pintype "passive"))
      (node (ref "TP2") (pin "P$1") (pinfunction "1_P$1") (pintype "bidirectional"))
      (node (ref "U4") (pin "3") (pinfunction "EN_3") (pintype "input"))
    )
    (net (code "2") (name "/BATT_STAT") (class "Default")
      (node (ref "C22") (pin "1") (pinfunction "1_1") (pintype "passive"))
      (node (ref "GND") (pin "27") (pinfunction "PD7(ADC10)_27") (pintype "bidirectional"))
      (node (ref "R1") (pin "2") (pinfunction "2_2") (pintype "passive"))
      (node (ref "R17") (pin "1") (pinfunction "1_1") (pintype "passive"))
      (node (ref "TP3") (pin "P$1") (pinfunction "1_P$1") (pintype "bidirectional"))
      (node (ref "U$3") (pin "27") (pinfunction "PD7(ADC10)_27") (pintype "bidirectional"))
    )
    (net (code "3") (name "/DATA1") (class "Default")
      (node (ref "GND") (pin "37") (pinfunction "PF6(ADC6)_37") (pintype "bidirectional"))
      (node (ref "ICSP1") (pin "4") (pinfunction "4_4") (pintype "bidirectional"))
      (node (ref "U$3") (pin "37") (pinfunction "PF6(ADC6)_37") (pintype "bidirectional"))
    )
    (net (code "4") (name "/DATA2") (class "Default")
      (node (ref "GND") (pin "36") (pinfunction "PF7(ADC7)_36") (pintype "bidirectional"))
      (node (ref "ICSP1") (pin "3") (pinfunction "3_3") (pintype "bidirectional"))
      (node (ref "U$3") (pin "36") (pinfunction "PF7(ADC7)_36") (pintype "bidirectional"))
    )
    (net (code "5") (name "/FLASH_CS") (class "Default")
      (node (ref "GND") (pin "32") (pinfunction "PC7_32") (pintype "bidirectional"))
      (node (ref "TP6") (pin "P$1") (pinfunction "1_P$1") (pintype "bidirectional"))
      (node (ref "U$3") (pin "32") (pinfunction "PC7_32") (pintype "bidirectional"))
      (node (ref "U$4") (pin "1") (pinfunction "~{CS}_1") (pintype "bidirectional"))
    )
    (net (code "6") (name "/ISOTHERMAL") (class "Default")
      (node (ref "C13") (pin "2") (pinfunction "2_2") (pintype "passive"))
      (node (ref "C14") (pin "2") (pinfunction "2_2") (pintype "passive"))
      (node (ref "C15") (pin "2") (pinfunction "2_2") (pintype "passive"))
      (node (ref "C16") (pin "2") (pinfunction "2_2") (pintype "passive"))
      (node (ref "C17") (pin "1") (pinfunction "1_1") (pintype "passive"))
      (node (ref "C24") (pin "1") (pinfunction "1_1") (pintype "passive"))
      (node (ref "C25") (pin "1") (pinfunction "1_1") (pintype "passive"))
      (node (ref "C31") (pin "2") (pinfunction "2_2") (pintype "passive"))
      (node (ref "C37") (pin "1") (pinfunction "1_1") (pintype "passive"))
      (node (ref "R31") (pin "1") (pinfunction "1_1") (pintype "passive"))
      (node (ref "R32") (pin "1") (pinfunction "1_1") (pintype "passive"))
      (node (ref "R33") (pin "1") (pinfunction "1_1") (pintype "passive"))
      (node (ref "R34") (pin "1") (pinfunction "1_1") (pintype "passive"))
      (node (ref "SJ2") (pin "2") (pinfunction "2_2") (pintype "passive"))
      (node (ref "TP8") (pin "P$1") (pinfunction "1_P$1") (pintype "bidirectional"))
      (node (ref "U1") (pin "2") (pinfunction "2_2") (pintype "bidirectional"))
    )
    (net (code "7") (name "/LCD_A0") (class "Default")
      (node (ref "GND") (pin "38") (pinfunction "PF5(ADC5)_38") (pintype "bidirectional"))
      (node (ref "U$3") (pin "38") (pinfunction "PF5(ADC5)_38") (pintype "bidirectional"))
      (node (ref "X1") (pin "8") (pinfunction "1_8") (pintype "passive"))
    )
    (net (code "8") (name "/LCD_BL") (class "Default")
      (node (ref "GND") (pin "41") (pinfunction "PF0(ADC0)_41") (pintype "bidirectional"))
      (node (ref "R19") (pin "2") (pinfunction "2_2") (pintype "passive"))
      (node (ref "TP5") (pin "P$1") (pinfunction "1_P$1") (pintype "bidirectional"))
      (node (ref "U$3") (pin "41") (pinfunction "PF0(ADC0)_41") (pintype "bidirectional"))
    )
    (net (code "9") (name "/LCD_CS") (class "Default")
      (node (ref "GND") (pin "40") (pinfunction "PF1(ADC1)_40") (pintype "bidirectional"))
      (node (ref "U$3") (pin "40") (pinfunction "PF1(ADC1)_40") (pintype "bidirectional"))
      (node (ref "X1") (pin "10") (pinfunction "1_10") (pintype "passive"))
    )
    (net (code "10") (name "/LCD_RST") (class "Default")
      (node (ref "GND") (pin "39") (pinfunction "PF4(ADC4)_39") (pintype "bidirectional"))
      (node (ref "U$3") (pin "39") (pinfunction "PF4(ADC4)_39") (pintype "bidirectional"))
      (node (ref "X1") (pin "9") (pinfunction "1_9") (pintype "passive"))
    )
    (net (code "11") (name "/MISO") (class "Default")
      (node (ref "GND") (pin "11") (pinfunction "PB3(MISO)_11") (pintype "bidirectional"))
      (node (ref "ICSP") (pin "1") (pinfunction "1_1") (pintype "bidirectional"))
      (node (ref "J1") (pin "7") (pinfunction "DO_7") (pintype "bidirectional"))
      (node (ref "U$3") (pin "11") (pinfunction "PB3(MISO)_11") (pintype "bidirectional"))
      (node (ref "U$4") (pin "2") (pinfunction "DO_2") (pintype "bidirectional"))
    )
    (net (code "12") (name "/MOSI") (class "Default")
      (node (ref "GND") (pin "10") (pinfunction "PB2(MOSI)_10") (pintype "bidirectional"))
      (node (ref "ICSP") (pin "4") (pinfunction "4_4") (pintype "bidirectional"))
      (node (ref "J1") (pin "3") (pinfunction "DI_3") (pintype "bidirectional"))
      (node (ref "U$3") (pin "10") (pinfunction "PB2(MOSI)_10") (pintype "bidirectional"))
      (node (ref "U$4") (pin "5") (pinfunction "DI_5") (pintype "bidirectional"))
      (node (ref "X1") (pin "6") (pinfunction "1_6") (pintype "passive"))
    )
    (net (code "13") (name "/PWR_ONOFF") (class "Default")
      (node (ref "GND") (pin "12") (pinfunction "PB7_12") (pintype "bidirectional"))
      (node (ref "Q4") (pin "1") (pinfunction "G_1") (pintype "passive"))
      (node (ref "R22") (pin "1") (pinfunction "1_1") (pintype "passive"))
      (node (ref "TP1") (pin "P$1") (pinfunction "1_P$1") (pintype "bidirectional"))
      (node (ref "U$3") (pin "12") (pinfunction "PB7_12") (pintype "bidirectional"))
    )
    (net (code "14") (name "/RESET") (class "Default")
      (node (ref "GND") (pin "13") (pinfunction "~{RESET}_13") (pintype "bidirectional"))
      (node (ref "ICSP") (pin "5") (pinfunction "5_5") (pintype "bidirectional"))
      (node (ref "R4") (pin "1") (pinfunction "1_1") (pintype "passive"))
      (node (ref "U$3") (pin "13") (pinfunction "~{RESET}_13") (pintype "bidirectional"))
    )
    (net (code "15") (name "/RTC_BATT") (class "Default")
      (node (ref "BAT1") (pin "PWR@1") (pinfunction "+_PWR@1") (pintype "power_in"))
      (node (ref "U$14") (pin "6") (pinfunction "VBAT_6") (pintype "input"))
    )
    (net (code "16") (name "/RTC_INT") (class "Default")
      (node (ref "GND") (pin "1") (pinfunction "PE6_1") (pintype "bidirectional"))
      (node (ref "R2") (pin "2") (pinfunction "2_2") (pintype "passive"))
      (node (ref "U$14") (pin "3") (pinfunction "INT/SQW_3") (pintype "output"))
      (node (ref "U$3") (pin "1") (pinfunction "PE6_1") (pintype "bidirectional"))
    )
    (net (code "17") (name "/SCK") (class "Default")
      (node (ref "GND") (pin "9") (pinfunction "PB1(SCK)_9") (pintype "bidirectional"))
      (node (ref "ICSP") (pin "3") (pinfunction "3_3") (pintype "bidirectional"))
      (node (ref "J1") (pin "5") (pinfunction "SCLK_5") (pintype "bidirectional"))
      (node (ref "U$3") (pin "9") (pinfunction "PB1(SCK)_9") (pintype "bidirectional"))
      (node (ref "U$4") (pin "6") (pinfunction "CLK_6") (pintype "bidirectional"))
      (node (ref "X1") (pin "7") (pinfunction "1_7") (pintype "passive"))
    )
    (net (code "18") (name "/SCL") (class "Default")
      (node (ref "GND") (pin "18") (pinfunction "PD0(SCL)_18") (pintype "bidirectional"))
      (node (ref "IC1") (pin "8") (pinfunction "SCL_8") (pintype "input"))
      (node (ref "ICSP1") (pin "1") (pinfunction "1_1") (pintype "bidirectional"))
      (node (ref "R14") (pin "1") (pinfunction "1_1") (pintype "passive"))
      (node (ref "U$14") (pin "8") (pinfunction "SCL_8") (pintype "input"))
      (node (ref "U$3") (pin "18") (pinfunction "PD0(SCL)_18") (pintype "bidirectional"))
      (node (ref "U1") (pin "4") (pinfunction "4_4") (pintype "bidirectional"))
    )
    (net (code "19") (name "/SDA") (class "Default")
      (node (ref "GND") (pin "19") (pinfunction "PD1(SDA)_19") (pintype "bidirectional"))
      (node (ref "IC1") (pin "7") (pinfunction "SDA_7") (pintype "bidirectional"))
      (node (ref "ICSP1") (pin "2") (pinfunction "2_2") (pintype "bidirectional"))
      (node (ref "R13") (pin "1") (pinfunction "1_1") (pintype "passive"))
      (node (ref "U$14") (pin "7") (pinfunction "SDA_7") (pintype "bidirectional"))
      (node (ref "U$3") (pin "19") (pinfunction "PD1(SDA)_19") (pintype "bidirectional"))
      (node (ref "U1") (pin "5") (pinfunction "5_5") (pintype "bidirectional"))
    )
    (net (code "20") (name "/SD_CS") (class "Default")
      (node (ref "GND") (pin "31") (pinfunction "PC6_31") (pintype "bidirectional"))
      (node (ref "J1") (pin "2") (pinfunction "CS_2") (pintype "bidirectional"))
      (node (ref "TP7") (pin "P$1") (pinfunction "1_P$1") (pintype "bidirectional"))
      (node (ref "U$3") (pin "31") (pinfunction "PC6_31") (pintype "bidirectional"))
    )
    (net (code "21") (name "/SW_PWR") (class "Default")
      (node (ref "GND") (pin "8") (pinfunction "PB0(SS)_8") (pintype "bidirectional"))
      (node (ref "Q5") (pin "3") (pinfunction "D_3") (pintype "passive"))
      (node (ref "R18") (pin "1") (pinfunction "1_1") (pintype "passive"))
      (node (ref "TP9") (pin "P$1") (pinfunction "1_P$1") (pintype "bidirectional"))
      (node (ref "U$3") (pin "8") (pinfunction "PB0(SS)_8") (pintype "bidirectional"))
    )
    (net (code "22") (name "/TC1+") (class "Default")
      (node (ref "C10") (pin "1") (pinfunction "1_1") (pintype "passive"))
      (node (ref "C16") (pin "1") (pinfunction "1_1") (pintype "passive"))
      (node (ref "IC1") (pin "3") (pinfunction "CH2+_3") (pintype "input"))
      (node (ref "R39") (pin "1") (pinfunction "1_1") (pintype "passive"))
    )
    (net (code "23") (name "/TC1-") (class "Default")
      (node (ref "C10") (pin "2") (pinfunction "2_2") (pintype "passive"))
      (node (ref "C15") (pin "1") (pinfunction "1_1") (pintype "passive"))
      (node (ref "IC1") (pin "4") (pinfunction "CH2-_4") (pintype "input"))
      (node (ref "R41") (pin "2") (pinfunction "2_2") (pintype "passive"))
    )
    (net (code "24") (name "/TC2+") (class "Default")
      (node (ref "C11") (pin "1") (pinfunction "1_1") (pintype "passive"))
      (node (ref "C14") (pin "1") (pinfunction "1_1") (pintype "passive"))
      (node (ref "IC1") (pin "1") (pinfunction "CH1+_1") (pintype "input"))
      (node (ref "R40") (pin "1") (pinfunction "1_1") (pintype "passive"))
    )
    (net (code "25") (name "/TC2-") (class "Default")
      (node (ref "C11") (pin "2") (pinfunction "2_2") (pintype "passive"))
      (node (ref "C13") (pin "1") (pinfunction "1_1") (pintype "passive"))
      (node (ref "IC1") (pin "2") (pinfunction "CH1-_2") (pintype "input"))
      (node (ref "R42") (pin "2") (pinfunction "2_2") (pintype "passive"))
    )
    (net (code "26") (name "/TC3+") (class "Default")
      (node (ref "C17") (pin "2") (pinfunction "2_2") (pintype "passive"))
      (node (ref "C7") (pin "1") (pinfunction "1_1") (pintype "passive"))
      (node (ref "IC1") (pin "13") (pinfunction "CH4+_13") (pintype "input"))
      (node (ref "R35") (pin "1") (pinfunction "1_1") (pintype "passive"))
    )
    (net (code "27") (name "/TC3-") (class "Default")
      (node (ref "C24") (pin "2") (pinfunction "2_2") (pintype "passive"))
      (node (ref "C7") (pin "2") (pinfunction "2_2") (pintype "passive"))
      (node (ref "IC1") (pin "14") (pinfunction "CH4-_14") (pintype "input"))
      (node (ref "R36") (pin "2") (pinfunction "2_2") (pintype "passive"))
    )
    (net (code "28") (name "/TC4+") (class "Default")
      (node (ref "C25") (pin "2") (pinfunction "2_2") (pintype "passive"))
      (node (ref "C8") (pin "1") (pinfunction "1_1") (pintype "passive"))
      (node (ref "IC1") (pin "11") (pinfunction "CH3+_11") (pintype "input"))
      (node (ref "R37") (pin "1") (pinfunction "1_1") (pintype "passive"))
    )
    (net (code "29") (name "/TC4-") (class "Default")
      (node (ref "C37") (pin "2") (pinfunction "2_2") (pintype "passive"))
      (node (ref "C8") (pin "2") (pinfunction "2_2") (pintype "passive"))
      (node (ref "IC1") (pin "12") (pinfunction "CH3-_12") (pintype "input"))
      (node (ref "R38") (pin "2") (pinfunction "2_2") (pintype "passive"))
    )
    (net (code "30") (name "/TXLED") (class "Default")
      (node (ref "GND") (pin "22") (pinfunction "PD5_22") (pintype "bidirectional"))
      (node (ref "U$3") (pin "22") (pinfunction "PD5_22") (pintype "bidirectional"))
    )
    (net (code "31") (name "/USBVCC") (class "Default")
      (node (ref "F1") (pin "1") (pinfunction "1_1") (pintype "bidirectional"))
      (node (ref "ICSP") (pin "2") (pinfunction "2_2") (pintype "bidirectional"))
      (node (ref "TP10") (pin "P$1") (pinfunction "1_P$1") (pintype "bidirectional"))
      (node (ref "U$1") (pin "PIN$1") (pinfunction "VCC_PIN$1") (pintype "bidirectional"))
    )
    (net (code "32") (name "/VBAT") (class "Default")
      (node (ref "C9") (pin "1") (pinfunction "1_1") (pintype "passive"))
      (node (ref "Q1") (pin "3") (pinfunction "D_3") (pintype "passive"))
      (node (ref "Q2") (pin "2") (pinfunction "S_2") (pintype "passive"))
      (node (ref "R5") (pin "1") (pinfunction "1_1") (pintype "passive"))
      (node (ref "SJ1") (pin "1") (pinfunction "1_1") (pintype "passive"))
      (node (ref "TP14") (pin "P$1") (pinfunction "1_P$1") (pintype "bidirectional"))
      (node (ref "U3") (pin "3") (pinfunction "VBAT_3") (pintype "power_in"))
    )
    (net (code "33") (name "/VBAT_EN") (class "Default")
      (node (ref "GND") (pin "25") (pinfunction "PD4(ADC8)_25") (pintype "bidirectional"))
      (node (ref "Q3") (pin "1") (pinfunction "G_1") (pintype "passive"))
      (node (ref "R23") (pin "2") (pinfunction "2_2") (pintype "passive"))
      (node (ref "U$3") (pin "25") (pinfunction "PD4(ADC8)_25") (pintype "bidirectional"))
    )
    (net (code "34") (name "/VBAT_SENSE") (class "Default")
      (node (ref "GND") (pin "26") (pinfunction "PD6(ADC9)_26") (pintype "bidirectional"))
      (node (ref "R20") (pin "1") (pinfunction "1_1") (pintype "passive"))
      (node (ref "R24") (pin "1") (pinfunction "1_1") (pintype "passive"))
      (node (ref "TP4") (pin "P$1") (pinfunction "1_P$1") (pintype "bidirectional"))
      (node (ref "U$3") (pin "26") (pinfunction "PD6(ADC9)_26") (pintype "bidirectional"))
    )
    (net (code "35") (name "/VBUS") (class "Default")
      (node (ref "C1") (pin "1") (pinfunction "1_1") (pintype "passive"))
      (node (ref "C12") (pin "1") (pinfunction "1_1") (pintype "passive"))
      (node (ref "C2") (pin "1") (pinfunction "1_1") (pintype "passive"))
      (node (ref "C28") (pin "1") (pinfunction "1_1") (pintype "passive"))
      (node (ref "D2") (pin "C") (pinfunction "C_C") (pintype "passive"))
      (node (ref "GND") (pin "7") (pinfunction "VBUS_7") (pintype "bidirectional"))
      (node (ref "IC3") (pin "8") (pinfunction "VCC_8") (pintype "power_in"))
      (node (ref "JP1") (pin "1") (pinfunction "1_1") (pintype "passive"))
      (node (ref "Q1") (pin "2") (pinfunction "S_2") (pintype "passive"))
      (node (ref "R6") (pin "1") (pinfunction "1_1") (pintype "passive"))
      (node (ref "R7") (pin "1") (pinfunction "1_1") (pintype "passive"))
      (node (ref "TP12") (pin "P$1") (pinfunction "1_P$1") (pintype "bidirectional"))
      (node (ref "U$3") (pin "7") (pinfunction "VBUS_7") (pintype "bidirectional"))
      (node (ref "U4") (pin "1") (pinfunction "IN_1") (pintype "input"))
    )
    (net (code "36") (name "/VBUS_IN") (class "Default")
      (node (ref "C6") (pin "1") (pinfunction "1_1") (pintype "passive"))
      (node (ref "D2") (pin "A") (pinfunction "A_A") (pintype "passive"))
      (node (ref "F1") (pin "2") (pinfunction "2_2") (pintype "bidirectional"))
      (node (ref "TP11") (pin "P$1") (pinfunction "1_P$1") (pintype "bidirectional"))
      (node (ref "U2") (pin "3") (pinfunction "VCC_3") (pintype "power_in"))
      (node (ref "U3") (pin "4") (pinfunction "VIN_4") (pintype "power_in"))
    )
    (net (code "37") (name "/XTAL1") (class "Default")
      (node (ref "GND") (pin "17") (pinfunction "XTAL1_17") (pintype "bidirectional"))
      (node (ref "U$3") (pin "17") (pinfunction "XTAL1_17") (pintype "bidirectional"))
      (node (ref "Y1") (pin "1") (pinfunction "1_1") (pintype "passive"))
    )
    (net (code "38") (name "/XTAL2") (class "Default")
      (node (ref "GND") (pin "16") (pinfunction "XTAL2_16") (pintype "bidirectional"))
      (node (ref "U$3") (pin "16") (pinfunction "XTAL2_16") (pintype "bidirectional"))
      (node (ref "Y1") (pin "3") (pinfunction "3_3") (pintype "passive"))
    )
    (net (code "39") (name "3.3V") (class "Default")
      (node (ref "C18") (pin "1") (pinfunction "1_1") (pintype "passive"))
      (node (ref "C19") (pin "1") (pinfunction "1_1") (pintype "passive"))
      (node (ref "C20") (pin "2") (pinfunction "2_2") (pintype "passive"))
      (node (ref "C21") (pin "2") (pinfunction "2_2") (pintype "passive"))
      (node (ref "C26") (pin "1") (pinfunction "1_1") (pintype "passive"))
      (node (ref "C27") (pin "1") (pinfunction "1_1") (pintype "passive"))
      (node (ref "C29") (pin "1") (pinfunction "1_1") (pintype "passive"))
      (node (ref "C30") (pin "1") (pinfunction "1_1") (pintype "passive"))
      (node (ref "C31") (pin "1") (pinfunction "1_1") (pintype "passive"))
      (node (ref "C32") (pin "1") (pinfunction "1_1") (pintype "passive"))
      (node (ref "C33") (pin "1") (pinfunction "1_1") (pintype "passive"))
      (node (ref "C34") (pin "1") (pinfunction "1_1") (pintype "passive"))
      (node (ref "C5") (pin "1") (pinfunction "1_1") (pintype "passive"))
      (node (ref "GND") (pin "14") (pinfunction "VCC_14") (pintype "bidirectional"))
      (node (ref "GND") (pin "24") (pinfunction "AVCC_24") (pintype "bidirectional"))
      (node (ref "GND") (pin "34") (pinfunction "VCC_34") (pintype "bidirectional"))
      (node (ref "GND") (pin "44") (pinfunction "AVCC_44") (pintype "bidirectional"))
      (node (ref "GND") (pin "6") (pinfunction "UCAP_6") (pintype "bidirectional"))
      (node (ref "IC1") (pin "6") (pinfunction "VDD_6") (pintype "power_in"))
      (node (ref "ICSP1") (pin "6") (pinfunction "6_6") (pintype "bidirectional"))
      (node (ref "J1") (pin "4") (pinfunction "VDD_4") (pintype "bidirectional"))
      (node (ref "Q5") (pin "2") (pinfunction "S_2") (pintype "passive"))
      (node (ref "R1") (pin "1") (pinfunction "1_1") (pintype "passive"))
      (node (ref "R11") (pin "1") (pinfunction "1_1") (pintype "passive"))
      (node (ref "R12") (pin "1") (pinfunction "1_1") (pintype "passive"))
      (node (ref "R13") (pin "2") (pinfunction "2_2") (pintype "passive"))
      (node (ref "R14") (pin "2") (pinfunction "2_2") (pintype "passive"))
      (node (ref "R15") (pin "1") (pinfunction "1_1") (pintype "passive"))
      (node (ref "R16") (pin "1") (pinfunction "1_1") (pintype "passive"))
      (node (ref "R2") (pin "1") (pinfunction "1_1") (pintype "passive"))
      (node (ref "R27") (pin "2") (pinfunction "2_2") (pintype "passive"))
      (node (ref "R28") (pin "2") (pinfunction "2_2") (pintype "passive"))
      (node (ref "R29") (pin "2") (pinfunction "2_2") (pintype "passive"))
      (node (ref "R30") (pin "2") (pinfunction "2_2") (pintype "passive"))
      (node (ref "R4") (pin "2") (pinfunction "2_2") (pintype "passive"))
      (node (ref "R8") (pin "1") (pinfunction "1_1") (pintype "passive"))
      (node (ref "TP13") (pin "P$1") (pinfunction "1_P$1") (pintype "bidirectional"))
      (node (ref "U$14") (pin "2") (pinfunction "VCC_2") (pintype "power_in"))
      (node (ref "U$3") (pin "14") (pinfunction "VCC_14") (pintype "bidirectional"))
      (node (ref "U$3") (pin "24") (pinfunction "AVCC_24") (pintype "bidirectional"))
      (node (ref "U$3") (pin "34") (pinfunction "VCC_34") (pintype "bidirectional"))
      (node (ref "U$3") (pin "44") (pinfunction "AVCC_44") (pintype "bidirectional"))
      (node (ref "U$3") (pin "6") (pinfunction "UCAP_6") (pintype "bidirectional"))
      (node (ref "U$4") (pin "3") (pinfunction "~{WP}_3") (pintype "bidirectional"))
      (node (ref "U$4") (pin "7") (pinfunction "~{HOLD}_7") (pintype "bidirectional"))
      (node (ref "U$4") (pin "8") (pinfunction "VCC_8") (pintype "bidirectional"))
      (node (ref "U1") (pin "1") (pinfunction "1_1") (pintype "bidirectional"))
      (node (ref "U4") (pin "5") (pinfunction "OUT_5") (pintype "passive"))
      (node (ref "X1") (pin "12") (pinfunction "1_12") (pintype "passive"))
      (node (ref "X1") (pin "5") (pinfunction "1_5") (pintype "passive"))
    )
    (net (code "40") (name "D+") (class "Default")
      (node (ref "GND") (pin "4") (pinfunction "D+_4") (pintype "bidirectional"))
      (node (ref "R9") (pin "2") (pinfunction "2_2") (pintype "passive"))
      (node (ref "U$3") (pin "4") (pinfunction "D+_4") (pintype "bidirectional"))
    )
    (net (code "41") (name "D-") (class "Default")
      (node (ref "GND") (pin "3") (pinfunction "D-_3") (pintype "bidirectional"))
      (node (ref "R10") (pin "2") (pinfunction "2_2") (pintype "passive"))
      (node (ref "U$3") (pin "3") (pinfunction "D-_3") (pintype "bidirectional"))
    )
    (net (code "42") (name "GND") (class "Default")
      (node (ref "BAT1") (pin "GND") (pinfunction "-_GND") (pintype "power_in"))
      (node (ref "C1") (pin "2") (pinfunction "2_2") (pintype "passive"))
      (node (ref "C12") (pin "2") (pinfunction "2_2") (pintype "passive"))
      (node (ref "C18") (pin "2") (pinfunction "2_2") (pintype "passive"))
      (node (ref "C19") (pin "2") (pinfunction "2_2") (pintype "passive"))
      (node (ref "C2") (pin "2") (pinfunction "2_2") (pintype "passive"))
      (node (ref "C20") (pin "1") (pinfunction "1_1") (pintype "passive"))
      (node (ref "C21") (pin "1") (pinfunction "1_1") (pintype "passive"))
      (node (ref "C22") (pin "2") (pinfunction "2_2") (pintype "passive"))
      (node (ref "C26") (pin "2") (pinfunction "2_2") (pintype "passive"))
      (node (ref "C27") (pin "2") (pinfunction "2_2") (pintype "passive"))
      (node (ref "C28") (pin "2") (pinfunction "2_2") (pintype "passive"))
      (node (ref "C29") (pin "2") (pinfunction "2_2") (pintype "passive"))
      (node (ref "C3") (pin "2") (pinfunction "2_2") (pintype "passive"))
      (node (ref "C30") (pin "2") (pinfunction "2_2") (pintype "passive"))
      (node (ref "C32") (pin "2") (pinfunction "2_2") (pintype "passive"))
      (node (ref "C33") (pin "2") (pinfunction "2_2") (pintype "passive"))
      (node (ref "C34") (pin "2") (pinfunction "2_2") (pintype "passive"))
      (node (ref "C36") (pin "1") (pinfunction "1_1") (pintype "passive"))
      (node (ref "C4") (pin "2") (pinfunction "2_2") (pintype "passive"))
      (node (ref "C5") (pin "2") (pinfunction "2_2") (pintype "passive"))
      (node (ref "C6") (pin "2") (pinfunction "2_2") (pintype "passive"))
      (node (ref "C9") (pin "2") (pinfunction "2_2") (pintype "passive"))
      (node (ref "GND") (pin "15") (pinfunction "GND_15") (pintype "bidirectional"))
      (node (ref "GND") (pin "23") (pinfunction "GND_23") (pintype "bidirectional"))
      (node (ref "GND") (pin "33") (pinfunction "PE2/~{HWB}_33") (pintype "bidirectional"))
      (node (ref "GND") (pin "35") (pinfunction "GND_35") (pintype "bidirectional"))
      (node (ref "GND") (pin "43") (pinfunction "GND_43") (pintype "bidirectional"))
      (node (ref "GND") (pin "5") (pinfunction "UGND_5") (pintype "bidirectional"))
      (node (ref "GND") (pin "P$1") (pinfunction "GND_PAD_P$1") (pintype "bidirectional"))
      (node (ref "IC1") (pin "5") (pinfunction "GND_5") (pintype "power_in"))
      (node (ref "IC1") (pin "9") (pinfunction "A0_9") (pintype "input"))
      (node (ref "IC3") (pin "1") (pinfunction "CLK_1") (pintype "input"))
      (node (ref "IC3") (pin "2") (pinfunction "D_2") (pintype "input"))
      (node (ref "IC3") (pin "4") (pinfunction "GND_4") (pintype "power_in"))
      (node (ref "ICSP") (pin "6") (pinfunction "6_6") (pintype "bidirectional"))
      (node (ref "ICSP1") (pin "5") (pinfunction "5_5") (pintype "bidirectional"))
      (node (ref "J1") (pin "6") (pinfunction "VSS_6") (pintype "bidirectional"))
      (node (ref "J1") (pin "G1") (pinfunction "G1_G1") (pintype "bidirectional"))
      (node (ref "J1") (pin "G2") (pinfunction "G2_G2") (pintype "bidirectional"))
      (node (ref "J1") (pin "G3") (pinfunction "G3_G3") (pintype "bidirectional"))
      (node (ref "J1") (pin "G4") (pinfunction "G4_G4") (pintype "bidirectional"))
      (node (ref "Q3") (pin "2") (pinfunction "S_2") (pintype "passive"))
      (node (ref "Q4") (pin "2") (pinfunction "S_2") (pintype "passive"))
      (node (ref "R18") (pin "2") (pinfunction "2_2") (pintype "passive"))
      (node (ref "R22") (pin "2") (pinfunction "2_2") (pintype "passive"))
      (node (ref "R23") (pin "1") (pinfunction "1_1") (pintype "passive"))
      (node (ref "R24") (pin "2") (pinfunction "2_2") (pintype "passive"))
      (node (ref "R3") (pin "2") (pinfunction "2_2") (pintype "passive"))
      (node (ref "S1") (pin "1") (pinfunction "1_1") (pintype "passive"))
      (node (ref "S2") (pin "1") (pinfunction "1_1") (pintype "passive"))
      (node (ref "S3") (pin "1") (pinfunction "1_1") (pintype "passive"))
      (node (ref "S4") (pin "1") (pinfunction "1_1") (pintype "passive"))
      (node (ref "S5") (pin "1") (pinfunction "1_1") (pintype "passive"))
      (node (ref "S6") (pin "3") (pinfunction "2_3") (pintype "passive"))
      (node (ref "SJ2") (pin "1") (pinfunction "1_1") (pintype "passive"))
      (node (ref "TP15") (pin "P$1") (pinfunction "1_P$1") (pintype "bidirectional"))
      (node (ref "U$1") (pin "PAD$1") (pinfunction "SHIELD_PAD$1") (pintype "bidirectional"))
      (node (ref "U$1") (pin "PAD$10") (pinfunction "SHIELD_PAD$10") (pintype "bidirectional"))
      (node (ref "U$1") (pin "PAD$2") (pinfunction "SHIELD_PAD$2") (pintype "bidirectional"))
      (node (ref "U$1") (pin "PAD$3") (pinfunction "SHIELD_PAD$3") (pintype "bidirectional"))
      (node (ref "U$1") (pin "PAD$4") (pinfunction "SHIELD_PAD$4") (pintype "bidirectional"))
      (node (ref "U$1") (pin "PAD$5") (pinfunction "SHIELD_PAD$5") (pintype "bidirectional"))
      (node (ref "U$1") (pin "PAD$6") (pinfunction "SHIELD_PAD$6") (pintype "bidirectional"))
      (node (ref "U$1") (pin "PAD$7") (pinfunction "SHIELD_PAD$7") (pintype "bidirectional"))
      (node (ref "U$1") (pin "PAD$8") (pinfunction "SHIELD_PAD$8") (pintype "bidirectional"))
      (node (ref "U$1") (pin "PAD$9") (pinfunction "SHIELD_PAD$9") (pintype "bidirectional"))
      (node (ref "U$1") (pin "PIN$5") (pinfunction "GND_PIN$5") (pintype "bidirectional"))
      (node (ref "U$14") (pin "5") (pinfunction "GND_5") (pintype "power_in"))
      (node (ref "U$2") (pin "P$3") (pinfunction "GND_P$3") (pintype "bidirectional"))
      (node (ref "U$2") (pin "P$4") (pinfunction "P$4_P$4") (pintype "bidirectional"))
      (node (ref "U$2") (pin "P$5") (pinfunction "P$5_P$5") (pintype "bidirectional"))
      (node (ref "U$3") (pin "15") (pinfunction "GND_15") (pintype "bidirectional"))
      (node (ref "U$3") (pin "23") (pinfunction "GND_23") (pintype "bidirectional"))
      (node (ref "U$3") (pin "33") (pinfunction "PE2/~{HWB}_33") (pintype "bidirectional"))
      (node (ref "U$3") (pin "35") (pinfunction "GND_35") (pintype "bidirectional"))
      (node (ref "U$3") (pin "43") (pinfunction "GND_43") (pintype "bidirectional"))
      (node (ref "U$3") (pin "5") (pinfunction "UGND_5") (pintype "bidirectional"))
      (node (ref "U$4") (pin "4") (pinfunction "GND_4") (pintype "bidirectional"))
      (node (ref "U2") (pin "1") (pinfunction "GND_1") (pintype "power_in"))
      (node (ref "U3") (pin "2") (pinfunction "VSS_2") (pintype "power_in"))
      (node (ref "U4") (pin "2") (pinfunction "GND_2") (pintype "input"))
      (node (ref "X1") (pin "4") (pinfunction "1_4") (pintype "passive"))
      (node (ref "Y1") (pin "2") (pinfunction "2_2") (pintype "passive"))
      (node (ref "Z1") (pin "1") (pinfunction "1_1") (pintype "passive"))
      (node (ref "Z2") (pin "1") (pinfunction "1_1") (pintype "passive"))
    )
    (net (code "43") (name "Net-(C36-Pad2)") (class "Default")
      (node (ref "C36") (pin "2") (pinfunction "2_2") (pintype "passive"))
      (node (ref "X1") (pin "1") (pinfunction "1_1") (pintype "passive"))
    )
    (net (code "44") (name "Net-(GND-AREF)") (class "Default")
      (node (ref "C3") (pin "1") (pinfunction "1_1") (pintype "passive"))
      (node (ref "GND") (pin "42") (pinfunction "AREF_42") (pintype "bidirectional"))
      (node (ref "U$3") (pin "42") (pinfunction "AREF_42") (pintype "bidirectional"))
    )
    (net (code "45") (name "Net-(GND-UVCC)") (class "Default")
      (node (ref "GND") (pin "2") (pinfunction "UVCC_2") (pintype "bidirectional"))
      (node (ref "U$3") (pin "2") (pinfunction "UVCC_2") (pintype "bidirectional"))
    )
    (net (code "46") (name "Net-(IC3-Q)") (class "Default")
      (node (ref "IC3") (pin "5") (pinfunction "Q_5") (pintype "output"))
      (node (ref "R21") (pin "1") (pinfunction "1_1") (pintype "passive"))
    )
    (net (code "47") (name "Net-(IC3-~{CLR})") (class "Default")
      (node (ref "IC3") (pin "6") (pinfunction "~{CLR}_6") (pintype "input"))
      (node (ref "Q4") (pin "3") (pinfunction "D_3") (pintype "passive"))
      (node (ref "R7") (pin "2") (pinfunction "2_2") (pintype "passive"))
    )
    (net (code "48") (name "Net-(IC3-~{SET})") (class "Default")
      (node (ref "IC3") (pin "7") (pinfunction "~{SET}_7") (pintype "input"))
      (node (ref "Q5") (pin "1") (pinfunction "G_1") (pintype "passive"))
      (node (ref "R6") (pin "2") (pinfunction "2_2") (pintype "passive"))
      (node (ref "S6") (pin "1") (pinfunction "1_1") (pintype "passive"))
    )
    (net (code "49") (name "Net-(Q1-G)") (class "Default")
      (node (ref "Q1") (pin "1") (pinfunction "G_1") (pintype "passive"))
      (node (ref "U2") (pin "2") (pinfunction "~{RST}_2") (pintype "bidirectional"))
    )
    (net (code "50") (name "Net-(Q2-D)") (class "Default")
      (node (ref "Q2") (pin "3") (pinfunction "D_3") (pintype "passive"))
      (node (ref "R20") (pin "2") (pinfunction "2_2") (pintype "passive"))
    )
    (net (code "51") (name "Net-(Q2-G)") (class "Default")
      (node (ref "Q2") (pin "1") (pinfunction "G_1") (pintype "passive"))
      (node (ref "Q3") (pin "3") (pinfunction "D_3") (pintype "passive"))
      (node (ref "R5") (pin "2") (pinfunction "2_2") (pintype "passive"))
    )
    (net (code "52") (name "Net-(R27-Pad1)") (class "Default")
      (node (ref "R27") (pin "1") (pinfunction "1_1") (pintype "passive"))
      (node (ref "R35") (pin "2") (pinfunction "2_2") (pintype "passive"))
      (node (ref "U$10") (pin "P$1") (pinfunction "P$1_P$1") (pintype "bidirectional"))
    )
    (net (code "53") (name "Net-(R28-Pad1)") (class "Default")
      (node (ref "R28") (pin "1") (pinfunction "1_1") (pintype "passive"))
      (node (ref "R37") (pin "2") (pinfunction "2_2") (pintype "passive"))
      (node (ref "U$11") (pin "P$1") (pinfunction "P$1_P$1") (pintype "bidirectional"))
    )
    (net (code "54") (name "Net-(R29-Pad1)") (class "Default")
      (node (ref "R29") (pin "1") (pinfunction "1_1") (pintype "passive"))
      (node (ref "R39") (pin "2") (pinfunction "2_2") (pintype "passive"))
      (node (ref "U$12") (pin "P$1") (pinfunction "P$1_P$1") (pintype "bidirectional"))
    )
    (net (code "55") (name "Net-(R30-Pad1)") (class "Default")
      (node (ref "R30") (pin "1") (pinfunction "1_1") (pintype "passive"))
      (node (ref "R40") (pin "2") (pinfunction "2_2") (pintype "passive"))
      (node (ref "U$13") (pin "P$1") (pinfunction "P$1_P$1") (pintype "bidirectional"))
    )
    (net (code "56") (name "Net-(R31-Pad2)") (class "Default")
      (node (ref "R31") (pin "2") (pinfunction "2_2") (pintype "passive"))
      (node (ref "R36") (pin "1") (pinfunction "1_1") (pintype "passive"))
      (node (ref "U$10") (pin "P$2") (pinfunction "P$2_P$2") (pintype "bidirectional"))
    )
    (net (code "57") (name "Net-(R32-Pad2)") (class "Default")
      (node (ref "R32") (pin "2") (pinfunction "2_2") (pintype "passive"))
      (node (ref "R38") (pin "1") (pinfunction "1_1") (pintype "passive"))
      (node (ref "U$11") (pin "P$2") (pinfunction "P$2_P$2") (pintype "bidirectional"))
    )
    (net (code "58") (name "Net-(R33-Pad2)") (class "Default")
      (node (ref "R33") (pin "2") (pinfunction "2_2") (pintype "passive"))
      (node (ref "R41") (pin "1") (pinfunction "1_1") (pintype "passive"))
      (node (ref "U$12") (pin "P$2") (pinfunction "P$2_P$2") (pintype "bidirectional"))
    )
    (net (code "59") (name "Net-(R34-Pad2)") (class "Default")
      (node (ref "R34") (pin "2") (pinfunction "2_2") (pintype "passive"))
      (node (ref "R42") (pin "1") (pinfunction "1_1") (pintype "passive"))
      (node (ref "U$13") (pin "P$2") (pinfunction "P$2_P$2") (pintype "bidirectional"))
    )
    (net (code "60") (name "Net-(U$1-D+)") (class "Default")
      (node (ref "R9") (pin "1") (pinfunction "1_1") (pintype "passive"))
      (node (ref "U$1") (pin "PIN$3") (pinfunction "D+_PIN$3") (pintype "bidirectional"))
      (node (ref "Z1") (pin "2") (pinfunction "2_2") (pintype "passive"))
    )
    (net (code "61") (name "Net-(U$1-D-)") (class "Default")
      (node (ref "R10") (pin "1") (pinfunction "1_1") (pintype "passive"))
      (node (ref "U$1") (pin "PIN$2") (pinfunction "D-_PIN$2") (pintype "bidirectional"))
      (node (ref "Z2") (pin "2") (pinfunction "2_2") (pintype "passive"))
    )
    (net (code "62") (name "Net-(U$2-VBAT)") (class "Default")
      (node (ref "SJ1") (pin "2") (pinfunction "2_2") (pintype "passive"))
      (node (ref "U$2") (pin "P$1") (pinfunction "VBAT_P$1") (pintype "bidirectional"))
    )
    (net (code "63") (name "Net-(U3-PROG)") (class "Default")
      (node (ref "R3") (pin "1") (pinfunction "1_1") (pintype "passive"))
      (node (ref "U3") (pin "5") (pinfunction "PROG_5") (pintype "input"))
    )
    (net (code "64") (name "Net-(U3-STAT)") (class "Default")
      (node (ref "R17") (pin "2") (pinfunction "2_2") (pintype "passive"))
      (node (ref "U3") (pin "1") (pinfunction "STAT_1") (pintype "output"))
    )
    (net (code "65") (name "Net-(U4-BP)") (class "Default")
      (node (ref "C4") (pin "1") (pinfunction "1_1") (pintype "passive"))
      (node (ref "U4") (pin "4") (pinfunction "BP_4") (pintype "input"))
    )
    (net (code "66") (name "Net-(X1C-1)") (class "Default")
      (node (ref "R19") (pin "1") (pinfunction "1_1") (pintype "passive"))
      (node (ref "X1") (pin "11") (pinfunction "1_11") (pintype "passive"))
    )
    (net (code "67") (name "Net-(X1E-1)") (class "Default")
      (node (ref "C35") (pin "2") (pinfunction "2_2") (pintype "passive"))
      (node (ref "X1") (pin "2") (pinfunction "1_2") (pintype "passive"))
    )
    (net (code "68") (name "Net-(X1F-1)") (class "Default")
      (node (ref "C35") (pin "1") (pinfunction "1_1") (pintype "passive"))
      (node (ref "X1") (pin "3") (pinfunction "1_3") (pintype "passive"))
    )
    (net (code "69") (name "SW_A") (class "Default")
      (node (ref "GND") (pin "21") (pinfunction "PD3(TX)_21") (pintype "bidirectional"))
      (node (ref "R8") (pin "2") (pinfunction "2_2") (pintype "passive"))
      (node (ref "S3") (pin "3") (pinfunction "2_3") (pintype "passive"))
      (node (ref "U$3") (pin "21") (pinfunction "PD3(TX)_21") (pintype "bidirectional"))
    )
    (net (code "70") (name "SW_B") (class "Default")
      (node (ref "GND") (pin "20") (pinfunction "PD2(RX)_20") (pintype "bidirectional"))
      (node (ref "R11") (pin "2") (pinfunction "2_2") (pintype "passive"))
      (node (ref "S2") (pin "3") (pinfunction "2_3") (pintype "passive"))
      (node (ref "U$3") (pin "20") (pinfunction "PD2(RX)_20") (pintype "bidirectional"))
    )
    (net (code "71") (name "SW_C") (class "Default")
      (node (ref "GND") (pin "28") (pinfunction "PB4(ADC11)_28") (pintype "bidirectional"))
      (node (ref "R12") (pin "2") (pinfunction "2_2") (pintype "passive"))
      (node (ref "S1") (pin "3") (pinfunction "2_3") (pintype "passive"))
      (node (ref "U$3") (pin "28") (pinfunction "PB4(ADC11)_28") (pintype "bidirectional"))
    )
    (net (code "72") (name "SW_D") (class "Default")
      (node (ref "GND") (pin "29") (pinfunction "PB5(ADC12)_29") (pintype "bidirectional"))
      (node (ref "R15") (pin "2") (pinfunction "2_2") (pintype "passive"))
      (node (ref "S4") (pin "3") (pinfunction "2_3") (pintype "passive"))
      (node (ref "U$3") (pin "29") (pinfunction "PB5(ADC12)_29") (pintype "bidirectional"))
    )
    (net (code "73") (name "SW_E") (class "Default")
      (node (ref "GND") (pin "30") (pinfunction "PB6(ADC13)_30") (pintype "bidirectional"))
      (node (ref "R16") (pin "2") (pinfunction "2_2") (pintype "passive"))
      (node (ref "S5") (pin "3") (pinfunction "2_3") (pintype "passive"))
      (node (ref "U$3") (pin "30") (pinfunction "PB6(ADC13)_30") (pintype "bidirectional"))
    )
    (net (code "74") (name "unconnected-(IC1-A1-Pad10)") (class "Default")
      (node (ref "IC1") (pin "10") (pinfunction "A1_10") (pintype "input"))
    )
    (net (code "75") (name "unconnected-(IC3-~{Q}-Pad3)") (class "Default")
      (node (ref "IC3") (pin "3") (pinfunction "~{Q}_3") (pintype "output"))
    )
    (net (code "76") (name "unconnected-(J1-CDN-Pad9)") (class "Default")
      (node (ref "J1") (pin "9") (pinfunction "CDN_9") (pintype "bidirectional"))
    )
    (net (code "77") (name "unconnected-(J1-DATA1-Pad8)") (class "Default")
      (node (ref "J1") (pin "8") (pinfunction "DATA1_8") (pintype "bidirectional"))
    )
    (net (code "78") (name "unconnected-(J1-DATA2-Pad1)") (class "Default")
      (node (ref "J1") (pin "1") (pinfunction "DATA2_1") (pintype "bidirectional"))
    )
    (net (code "79") (name "unconnected-(U$1-ID-PadPIN$4)") (class "Default")
      (node (ref "U$1") (pin "PIN$4") (pinfunction "ID_PIN$4") (pintype "bidirectional"))
    )
    (net (code "80") (name "unconnected-(U$2-BSI-PadP$2)") (class "Default")
      (node (ref "U$2") (pin "P$2") (pinfunction "BSI_P$2") (pintype "bidirectional"))
    )
    (net (code "81") (name "unconnected-(U$14-32KHZ-Pad1)") (class "Default")
      (node (ref "U$14") (pin "1") (pinfunction "32KHZ_1") (pintype "output"))
    )
    (net (code "82") (name "unconnected-(U$14-RST-Pad4)") (class "Default")
      (node (ref "U$14") (pin "4") (pinfunction "RST_4") (pintype "bidirectional"))
    )
    (net (code "83") (name "unconnected-(U1-Pad3)") (class "Default")
      (node (ref "U1") (pin "3") (pinfunction "3_3") (pintype "bidirectional"))
    )
  )
)
